# frankfurt_eth_pic.net
KiCad netlist of a schematic drawn in EAGLE
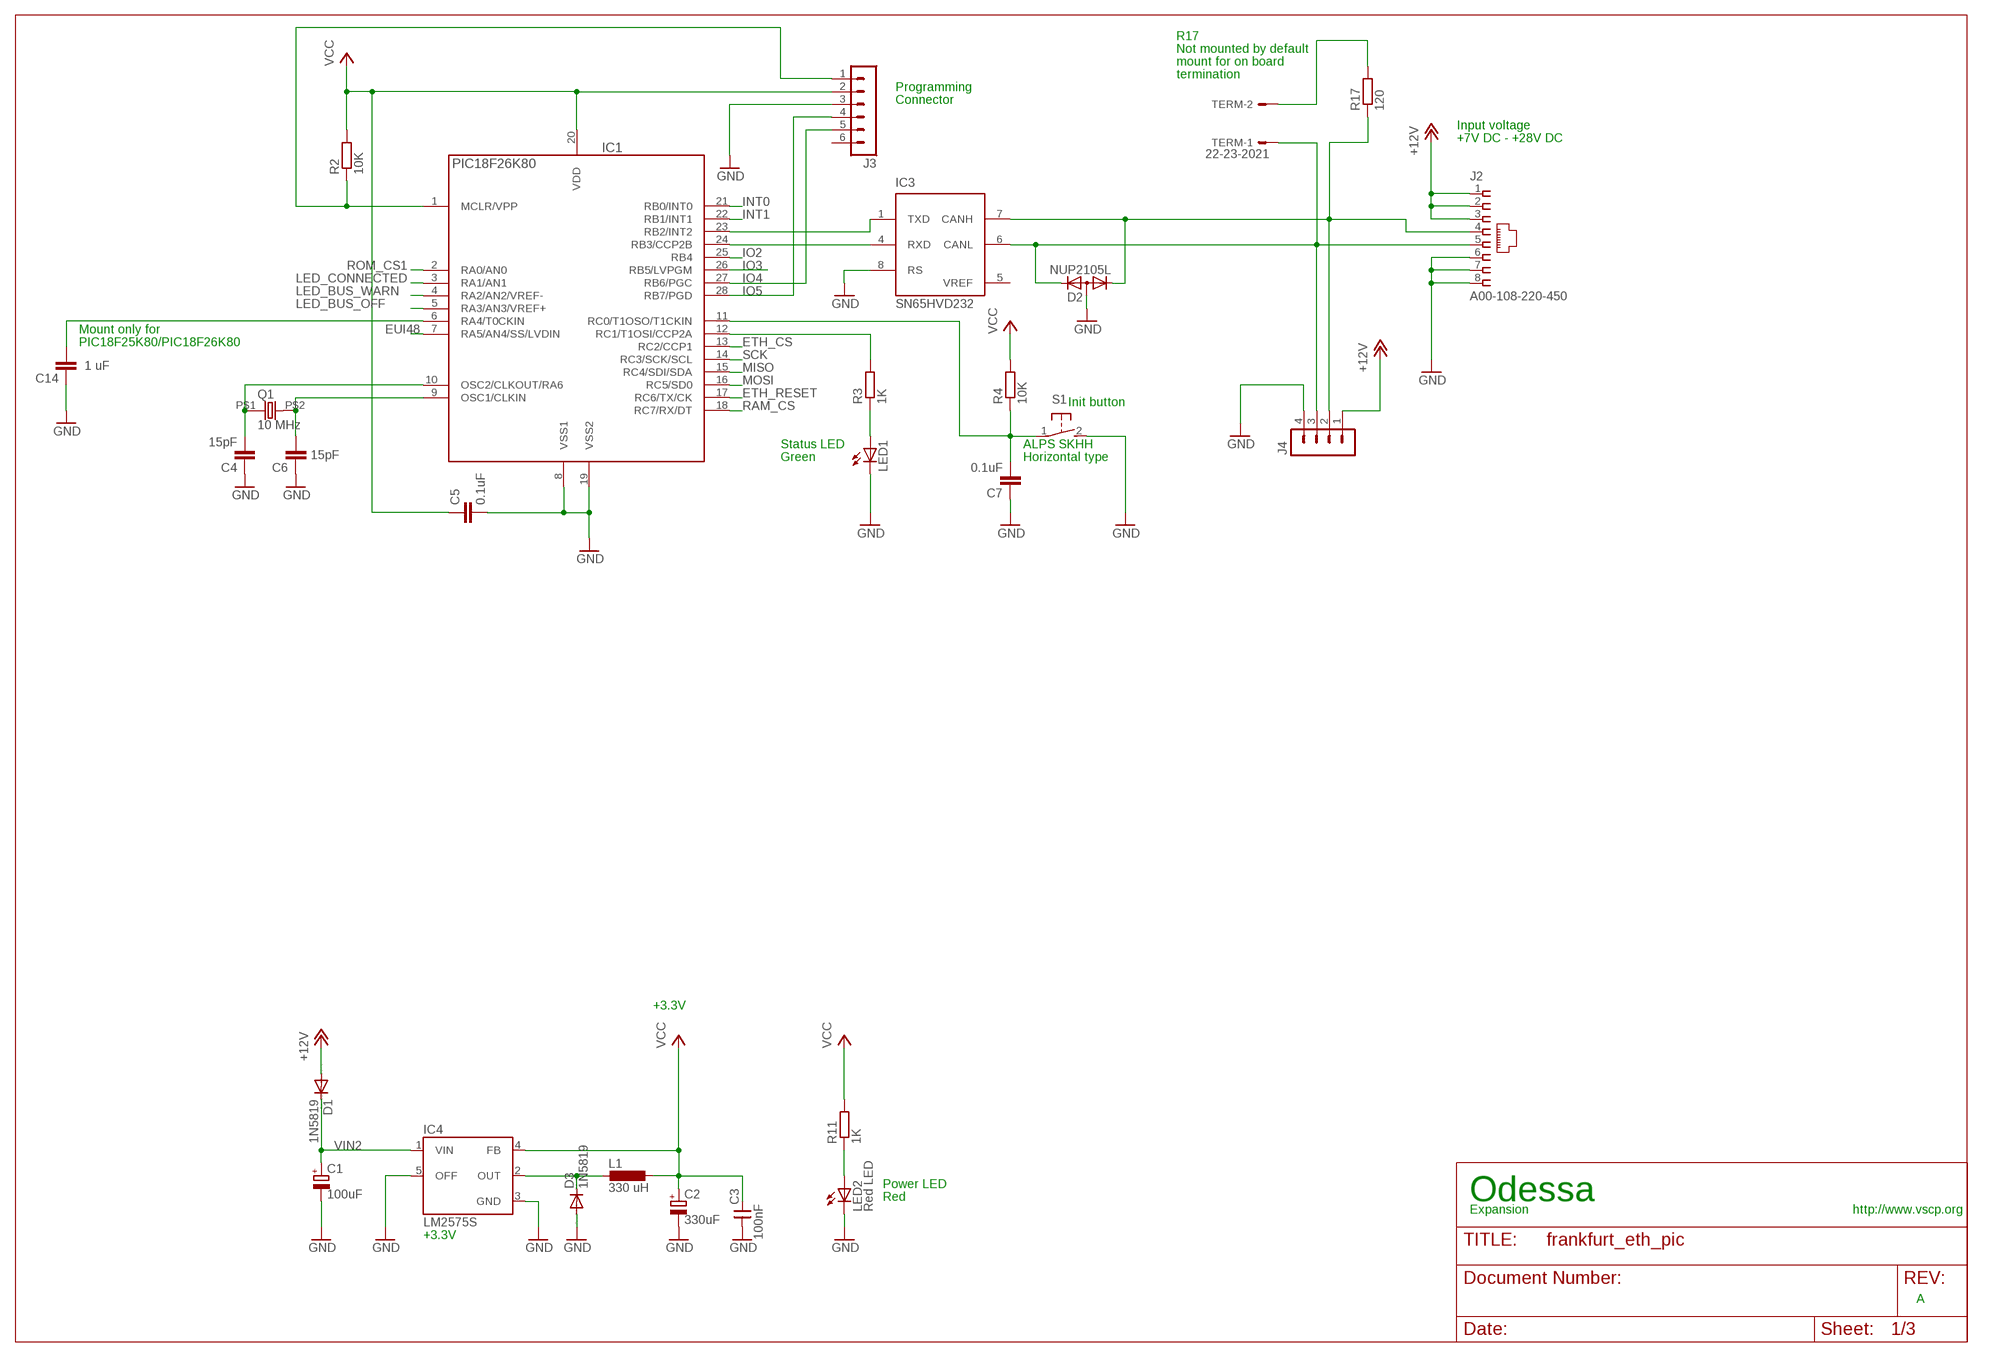
[diagram p0: schematic, sheet 1]
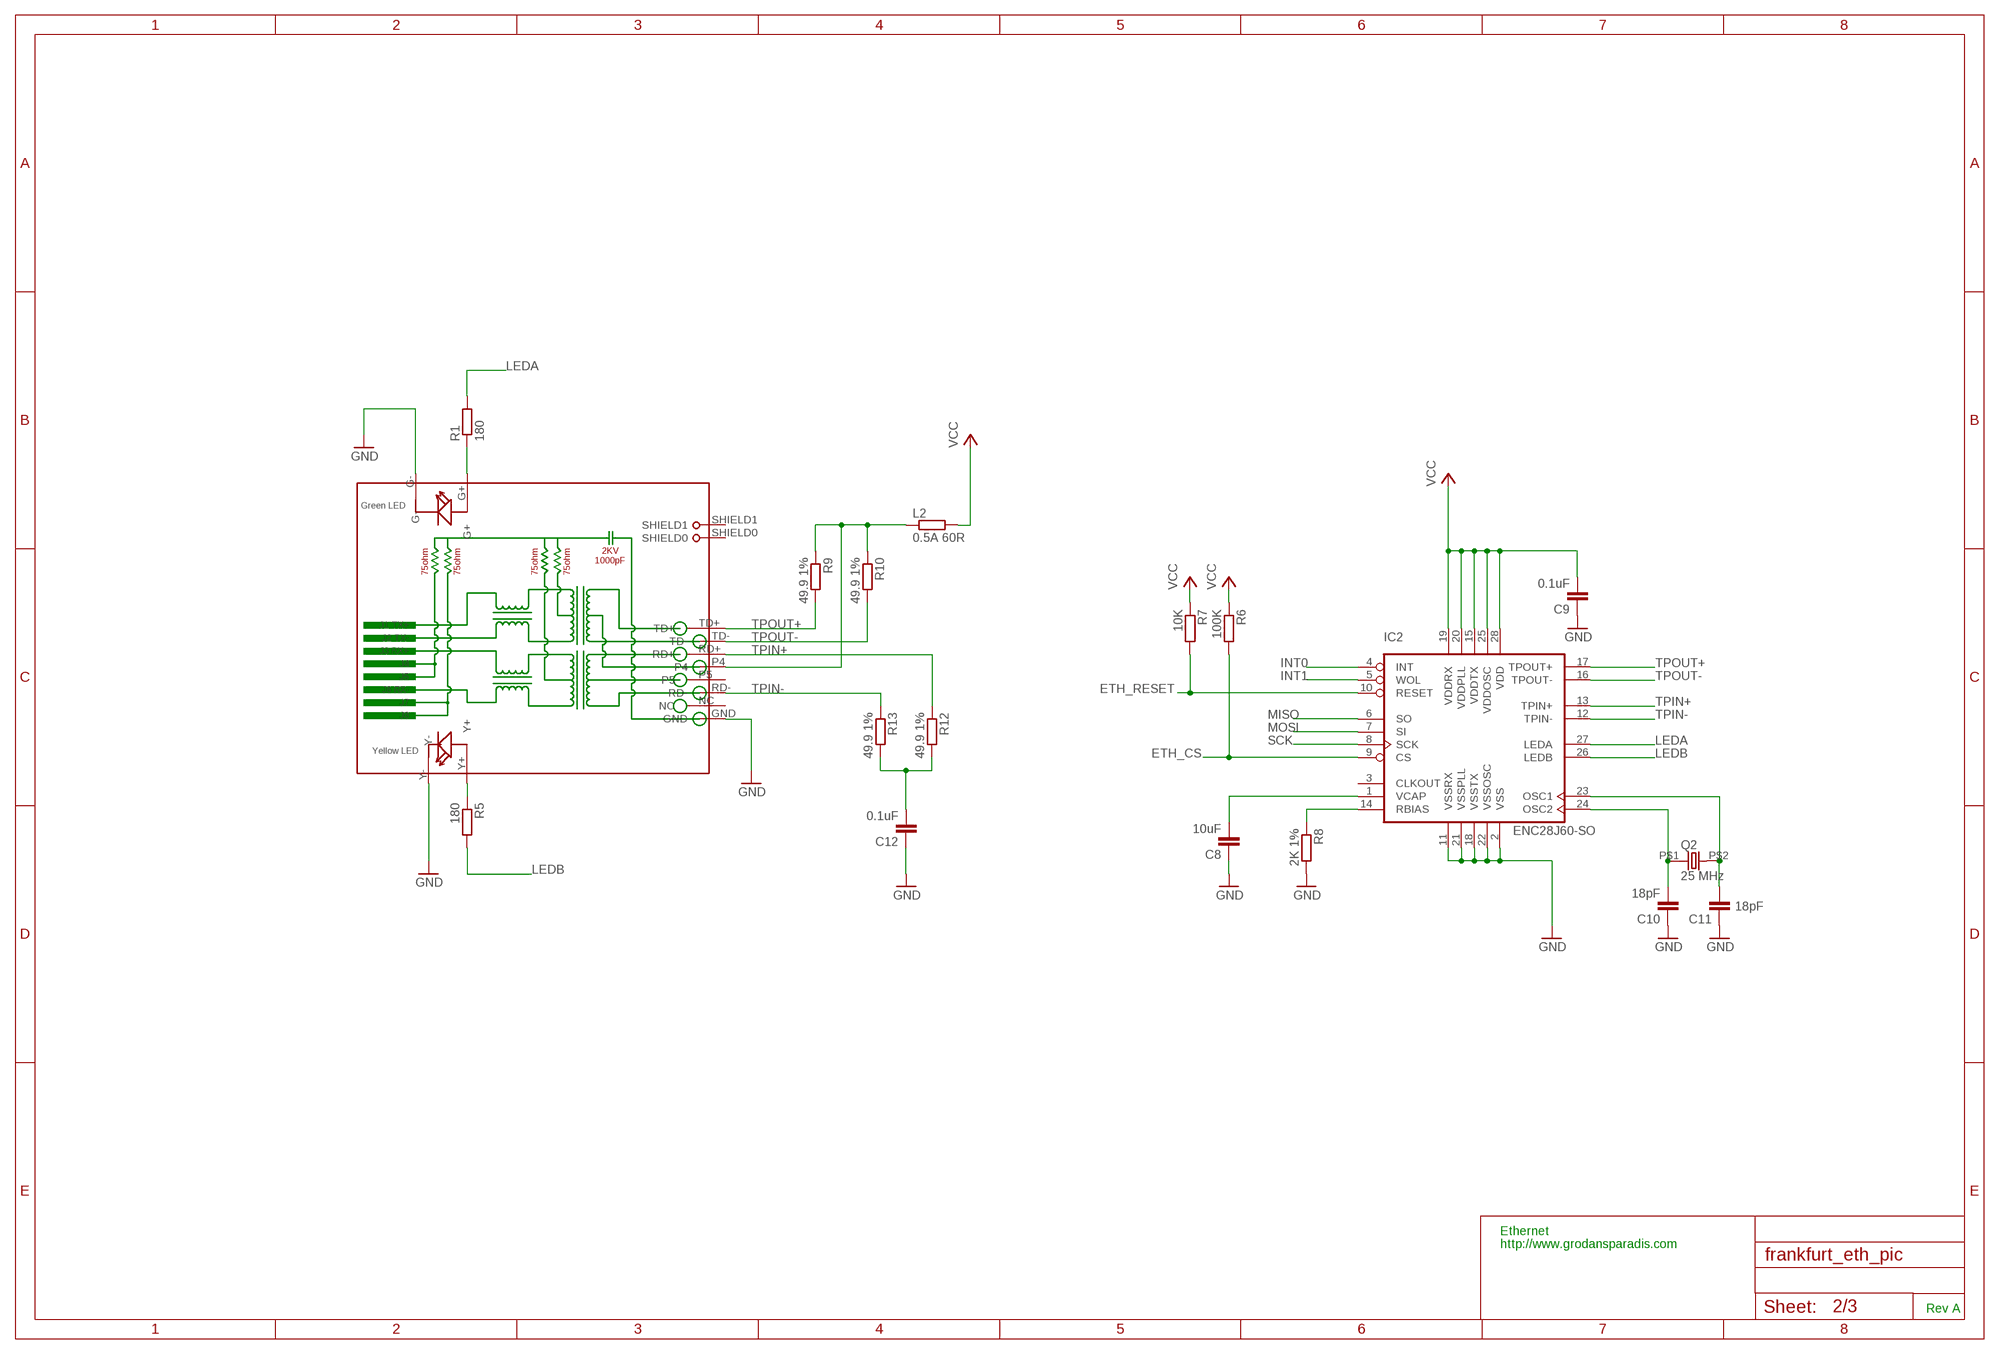
[diagram p1: schematic, sheet 2]
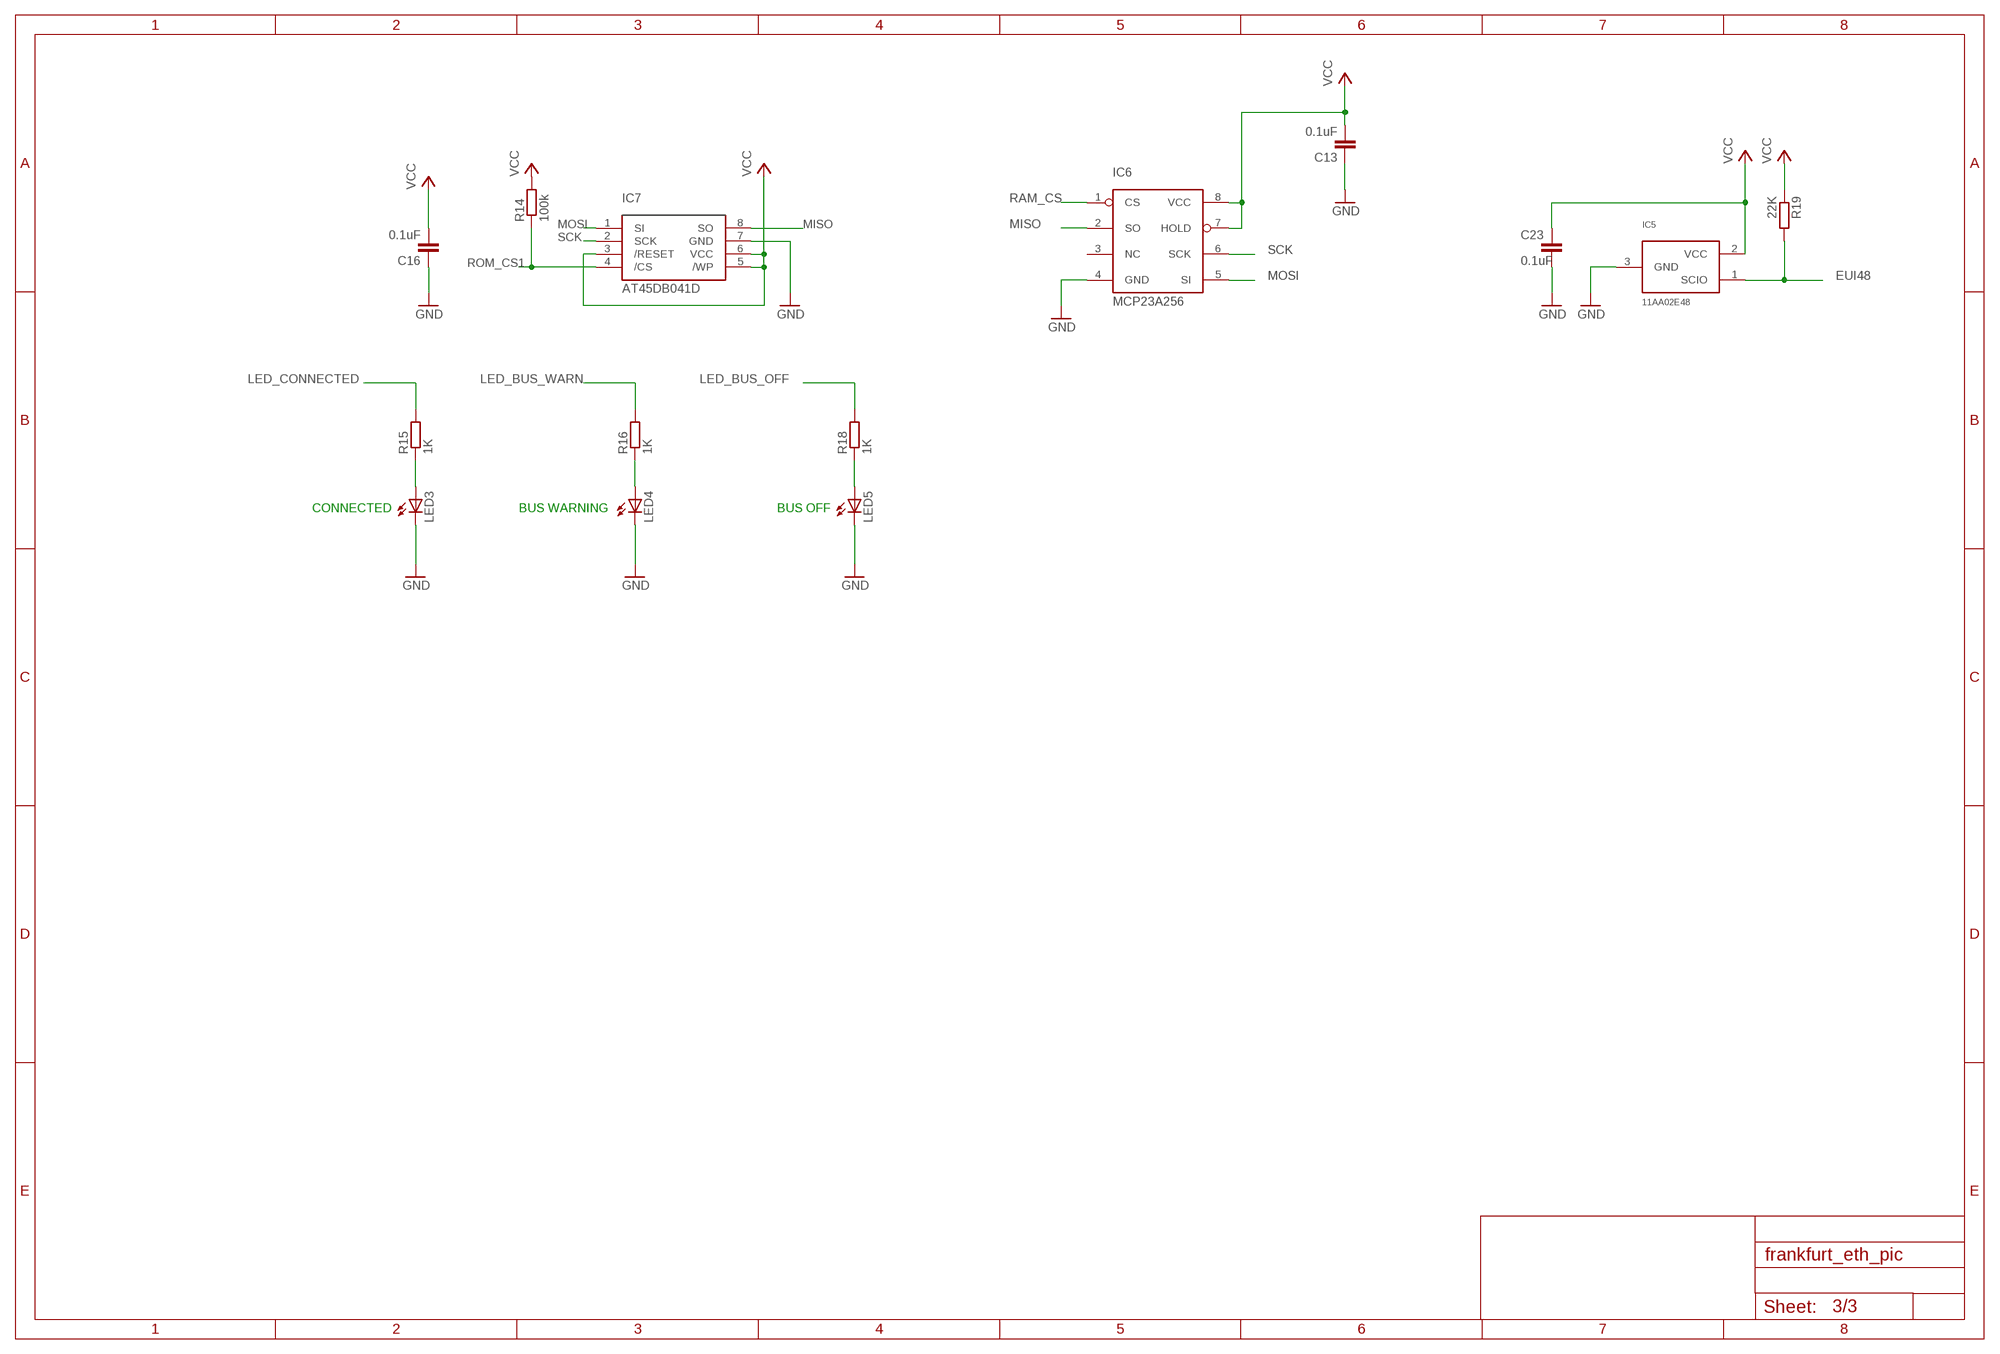
[diagram p2: schematic, sheet 3]

(export (version "E")
  (design (tool "Eeschema 10.0.6"))
  (components
    (comp (ref "C8")
      (value "10uF")
      (footprint "eagle-import:C0805")
      (libsource (lib "eagle-import") (part "C-EUC0805"))
    )
    (comp (ref "C9")
      (value "0.1uF")
      (footprint "eagle-import:C0805")
      (libsource (lib "eagle-import") (part "C-EUC0805"))
    )
    (comp (ref "C10")
      (value "18pF")
      (footprint "eagle-import:C0805")
      (libsource (lib "eagle-import") (part "C-EUC0805"))
    )
    (comp (ref "C11")
      (value "18pF")
      (footprint "eagle-import:C0805")
      (libsource (lib "eagle-import") (part "C-EUC0805"))
    )
    (comp (ref "C12")
      (value "0.1uF")
      (footprint "eagle-import:C0805")
      (libsource (lib "eagle-import") (part "C-EUC0805"))
    )
    (comp (ref "IC2")
      (value "ENC28J60-SO")
      (footprint "eagle-import:SO28W")
      (libsource (lib "eagle-import") (part "ENC28J60-SO"))
    )
    (comp (ref "L2")
      (value "0.5A 60R")
      (footprint "eagle-import:R0805")
      (libsource (lib "eagle-import") (part "R-EU_R0805"))
    )
    (comp (ref "Q2")
      (value "25 MHz")
      (footprint "eagle-import:9C")
      (libsource (lib "eagle-import") (part "HC-49S"))
    )
    (comp (ref "R1")
      (value "180")
      (footprint "eagle-import:R0805")
      (libsource (lib "eagle-import") (part "R-EU_R0805"))
    )
    (comp (ref "R5")
      (value "180")
      (footprint "eagle-import:R0805")
      (libsource (lib "eagle-import") (part "R-EU_R0805"))
    )
    (comp (ref "R6")
      (value "100K")
      (footprint "eagle-import:R0805")
      (libsource (lib "eagle-import") (part "R-EU_R0805"))
    )
    (comp (ref "R7")
      (value "10K")
      (footprint "eagle-import:R0805")
      (libsource (lib "eagle-import") (part "R-EU_R0805"))
    )
    (comp (ref "R8")
      (value "2K 1%")
      (footprint "eagle-import:R0805")
      (libsource (lib "eagle-import") (part "R-EU_R0805"))
    )
    (comp (ref "R9")
      (value "49.9 1%")
      (footprint "eagle-import:R0805")
      (libsource (lib "eagle-import") (part "R-EU_R0805"))
    )
    (comp (ref "R10")
      (value "49.9 1%")
      (footprint "eagle-import:R0805")
      (libsource (lib "eagle-import") (part "R-EU_R0805"))
    )
    (comp (ref "R12")
      (value "49.9 1%")
      (footprint "eagle-import:R0805")
      (libsource (lib "eagle-import") (part "R-EU_R0805"))
    )
    (comp (ref "R13")
      (value "49.9 1%")
      (footprint "eagle-import:R0805")
      (libsource (lib "eagle-import") (part "R-EU_R0805"))
    )
    (comp (ref "RJ1")
      (value "HR911105A")
      (footprint "eagle-import:HR911105A")
      (libsource (lib "eagle-import") (part "HR911105A"))
    )
    (comp (ref "C13")
      (value "0.1uF")
      (footprint "eagle-import:C0805")
      (libsource (lib "eagle-import") (part "C-EUC0805"))
    )
    (comp (ref "C16")
      (value "0.1uF")
      (footprint "eagle-import:C0805")
      (libsource (lib "eagle-import") (part "C-EUC0805"))
    )
    (comp (ref "C23")
      (value "0.1uF")
      (footprint "eagle-import:C0805")
      (libsource (lib "eagle-import") (part "C-EUC0805"))
    )
    (comp (ref "IC5")
      (value "11AA02E48")
      (footprint "eagle-import:SOT23")
      (libsource (lib "eagle-import") (part "11AA02E48"))
    )
    (comp (ref "IC6")
      (value "MCP23A256")
      (footprint "eagle-import:SO-8")
      (libsource (lib "eagle-import") (part "MCP23A256"))
    )
    (comp (ref "IC7")
      (value "AT45DB041D")
      (footprint "eagle-import:SOP8W")
      (libsource (lib "eagle-import") (part "AT45DB011DSOP8W"))
    )
    (comp (ref "LED3")
      (value "LEDCHIP-LED0805")
      (footprint "eagle-import:CHIP-LED0805")
      (libsource (lib "eagle-import") (part "LEDCHIP-LED0805"))
    )
    (comp (ref "LED4")
      (value "LEDCHIP-LED0805")
      (footprint "eagle-import:CHIP-LED0805")
      (libsource (lib "eagle-import") (part "LEDCHIP-LED0805"))
    )
    (comp (ref "LED5")
      (value "LEDCHIP-LED0805")
      (footprint "eagle-import:CHIP-LED0805")
      (libsource (lib "eagle-import") (part "LEDCHIP-LED0805"))
    )
    (comp (ref "R14")
      (value "100k")
      (footprint "eagle-import:M0805")
      (libsource (lib "eagle-import") (part "R-EU_M0805"))
    )
    (comp (ref "R15")
      (value "1K")
      (footprint "eagle-import:R0805")
      (libsource (lib "eagle-import") (part "R-EU_R0805"))
    )
    (comp (ref "R16")
      (value "1K")
      (footprint "eagle-import:R0805")
      (libsource (lib "eagle-import") (part "R-EU_R0805"))
    )
    (comp (ref "R18")
      (value "1K")
      (footprint "eagle-import:R0805")
      (libsource (lib "eagle-import") (part "R-EU_R0805"))
    )
    (comp (ref "R19")
      (value "22K")
      (footprint "eagle-import:M0805")
      (libsource (lib "eagle-import") (part "R-EU_M0805"))
    )
    (comp (ref "C1")
      (value "100uF")
      (footprint "eagle-import:PANASONIC_D")
      (libsource (lib "eagle-import") (part "CPOL-EUD"))
    )
    (comp (ref "C2")
      (value "330uF")
      (footprint "eagle-import:PANASONIC_D")
      (libsource (lib "eagle-import") (part "CPOL-EUD"))
    )
    (comp (ref "C3")
      (value "100nF")
      (footprint "eagle-import:0805")
      (libsource (lib "eagle-import") (part "CNP-0805"))
    )
    (comp (ref "C4")
      (value "15pF")
      (footprint "eagle-import:C0805")
      (libsource (lib "eagle-import") (part "C-EUC0805"))
    )
    (comp (ref "C5")
      (value "0.1uF")
      (footprint "eagle-import:C0805")
      (libsource (lib "eagle-import") (part "C-EUC0805"))
    )
    (comp (ref "C6")
      (value "15pF")
      (footprint "eagle-import:C0805")
      (libsource (lib "eagle-import") (part "C-EUC0805"))
    )
    (comp (ref "C7")
      (value "0.1uF")
      (footprint "eagle-import:C0805")
      (libsource (lib "eagle-import") (part "C-EUC0805"))
    )
    (comp (ref "C14")
      (value "1 uF")
      (footprint "eagle-import:C0805")
      (libsource (lib "eagle-import") (part "C-EUC0805"))
    )
    (comp (ref "D1")
      (value "1N5819")
      (footprint "eagle-import:SOD123")
      (libsource (lib "eagle-import") (part "DIODE-SOD123"))
    )
    (comp (ref "D2")
      (value "NUP2105L")
      (footprint "eagle-import:SOT23")
      (libsource (lib "eagle-import") (part "DIODE-2CA|ACSOT23"))
    )
    (comp (ref "D3")
      (value "1N5819")
      (footprint "eagle-import:SOD123")
      (libsource (lib "eagle-import") (part "DIODE-SOD123"))
    )
    (comp (ref "IC1")
      (value "PIC18F26K80")
      (footprint "eagle-import:SO28")
      (libsource (lib "eagle-import") (part "PIC18F252-?I/SOL"))
    )
    (comp (ref "IC3")
      (value "SN65HVD232")
      (footprint "eagle-import:SO-08")
      (libsource (lib "eagle-import") (part "MCP2551SN"))
    )
    (comp (ref "IC4")
      (value "LM2575S")
      (footprint "eagle-import:TO263-5")
      (libsource (lib "eagle-import") (part "LM2575S"))
    )
    (comp (ref "J2")
      (value "A00-108-220-450")
      (footprint "eagle-import:RJ-45")
      (libsource (lib "eagle-import") (part "A00-108-220-450"))
    )
    (comp (ref "J3")
      (value "MA06-1")
      (footprint "eagle-import:MA06-1")
      (libsource (lib "eagle-import") (part "MA06-1"))
    )
    (comp (ref "J4")
      (value "MA04-1")
      (footprint "eagle-import:MA04-1")
      (libsource (lib "eagle-import") (part "MA04-1"))
    )
    (comp (ref "L1")
      (value "330 uH")
      (footprint "eagle-import:DO3316P")
      (libsource (lib "eagle-import") (part "DO3316P"))
    )
    (comp (ref "LED1")
      (value "LEDCHIP-LED0805")
      (footprint "eagle-import:CHIP-LED0805")
      (libsource (lib "eagle-import") (part "LEDCHIP-LED0805"))
    )
    (comp (ref "LED2")
      (value "Red LED")
      (footprint "eagle-import:CHIP-LED0805")
      (libsource (lib "eagle-import") (part "LEDCHIP-LED0805"))
    )
    (comp (ref "Q1")
      (value "10 MHz")
      (footprint "eagle-import:9C")
      (libsource (lib "eagle-import") (part "HC-49S"))
    )
    (comp (ref "R2")
      (value "10K")
      (footprint "eagle-import:R0805")
      (libsource (lib "eagle-import") (part "R-EU_R0805"))
    )
    (comp (ref "R3")
      (value "1K")
      (footprint "eagle-import:R0805")
      (libsource (lib "eagle-import") (part "R-EU_R0805"))
    )
    (comp (ref "R4")
      (value "10K")
      (footprint "eagle-import:R0805")
      (libsource (lib "eagle-import") (part "R-EU_R0805"))
    )
    (comp (ref "R11")
      (value "1K")
      (footprint "eagle-import:R0805")
      (libsource (lib "eagle-import") (part "R-EU_R0805"))
    )
    (comp (ref "R17")
      (value "120")
      (footprint "eagle-import:R0805")
      (libsource (lib "eagle-import") (part "R-EU_R0805"))
    )
    (comp (ref "S1")
      (value "31-XX")
      (footprint "eagle-import:B3F-31XX")
      (fields (field (name "MPN") "B3F-3100"))
      (libsource (lib "eagle-import") (part "31-XX"))
    )
    (comp (ref "TERM")
      (value "22-23-2021")
      (footprint "eagle-import:22-23-2021")
      (fields (field (name "MF") "MOLEX"))
      (libsource (lib "eagle-import") (part "22-23-2021"))
    )
  )
  (nets
    (net (code "1") (name "+12V") (class "Default")
      (node (ref "D1") (pin "A") (pinfunction "A_A") (pintype "passive"))
      (node (ref "J2") (pin "1") (pinfunction "1_1") (pintype "passive"))
      (node (ref "J2") (pin "2") (pinfunction "2_2") (pintype "passive"))
      (node (ref "J2") (pin "3") (pinfunction "3_3") (pintype "passive"))
      (node (ref "J4") (pin "1") (pinfunction "1_1") (pintype "passive"))
    )
    (net (code "2") (name "ETH_CS") (class "Default")
      (node (ref "IC1") (pin "13") (pinfunction "RC2/CCP1_13") (pintype "bidirectional"))
      (node (ref "IC2") (pin "9") (pinfunction "CS_9") (pintype "input"))
      (node (ref "R6") (pin "2") (pinfunction "2_2") (pintype "passive"))
    )
    (net (code "3") (name "ETH_RESET") (class "Default")
      (node (ref "IC1") (pin "17") (pinfunction "RC6/TX/CK_17") (pintype "bidirectional"))
      (node (ref "IC2") (pin "10") (pinfunction "RESET_10") (pintype "input"))
      (node (ref "R7") (pin "2") (pinfunction "2_2") (pintype "passive"))
    )
    (net (code "4") (name "EUI48") (class "Default")
      (node (ref "IC1") (pin "7") (pinfunction "RA5/AN4/SS/LVDIN_7") (pintype "bidirectional"))
      (node (ref "IC5") (pin "1") (pinfunction "SCIO_1") (pintype "bidirectional"))
      (node (ref "R19") (pin "2") (pinfunction "2_2") (pintype "passive"))
    )
    (net (code "5") (name "GND") (class "Default")
      (node (ref "C1") (pin "-") (pinfunction "-_-") (pintype "passive"))
      (node (ref "C10") (pin "1") (pinfunction "1_1") (pintype "passive"))
      (node (ref "C11") (pin "1") (pinfunction "1_1") (pintype "passive"))
      (node (ref "C12") (pin "1") (pinfunction "1_1") (pintype "passive"))
      (node (ref "C13") (pin "1") (pinfunction "1_1") (pintype "passive"))
      (node (ref "C14") (pin "1") (pinfunction "1_1") (pintype "passive"))
      (node (ref "C16") (pin "1") (pinfunction "1_1") (pintype "passive"))
      (node (ref "C2") (pin "-") (pinfunction "-_-") (pintype "passive"))
      (node (ref "C23") (pin "2") (pinfunction "2_2") (pintype "passive"))
      (node (ref "C3") (pin "1") (pinfunction "1_1") (pintype "passive"))
      (node (ref "C4") (pin "1") (pinfunction "1_1") (pintype "passive"))
      (node (ref "C5") (pin "2") (pinfunction "2_2") (pintype "passive"))
      (node (ref "C6") (pin "1") (pinfunction "1_1") (pintype "passive"))
      (node (ref "C7") (pin "1") (pinfunction "1_1") (pintype "passive"))
      (node (ref "C8") (pin "1") (pinfunction "1_1") (pintype "passive"))
      (node (ref "C9") (pin "1") (pinfunction "1_1") (pintype "passive"))
      (node (ref "D2") (pin "3") (pinfunction "A_3") (pintype "passive"))
      (node (ref "D3") (pin "A") (pinfunction "A_A") (pintype "passive"))
      (node (ref "IC1") (pin "19") (pinfunction "VSS2_19") (pintype "power_in"))
      (node (ref "IC1") (pin "8") (pinfunction "VSS1_8") (pintype "power_in"))
      (node (ref "IC2") (pin "11") (pinfunction "VSSRX_11") (pintype "power_in"))
      (node (ref "IC2") (pin "18") (pinfunction "VSSTX_18") (pintype "power_in"))
      (node (ref "IC2") (pin "2") (pinfunction "VSS_2") (pintype "power_in"))
      (node (ref "IC2") (pin "21") (pinfunction "VSSPLL_21") (pintype "power_in"))
      (node (ref "IC2") (pin "22") (pinfunction "VSSOSC_22") (pintype "power_in"))
      (node (ref "IC3") (pin "8") (pinfunction "RS_8") (pintype "input"))
      (node (ref "IC4") (pin "3") (pinfunction "GND_3") (pintype "power_in"))
      (node (ref "IC4") (pin "5") (pinfunction "OFF_5") (pintype "input"))
      (node (ref "IC5") (pin "3") (pinfunction "GND_3") (pintype "power_in"))
      (node (ref "IC6") (pin "4") (pinfunction "GND_4") (pintype "power_in"))
      (node (ref "IC7") (pin "7") (pinfunction "GND_7") (pintype "power_in"))
      (node (ref "J2") (pin "6") (pinfunction "6_6") (pintype "passive"))
      (node (ref "J2") (pin "7") (pinfunction "7_7") (pintype "passive"))
      (node (ref "J2") (pin "8") (pinfunction "8_8") (pintype "passive"))
      (node (ref "J3") (pin "3") (pinfunction "3_3") (pintype "passive"))
      (node (ref "J4") (pin "4") (pinfunction "4_4") (pintype "passive"))
      (node (ref "LED1") (pin "C") (pinfunction "C_C") (pintype "passive"))
      (node (ref "LED2") (pin "C") (pinfunction "C_C") (pintype "passive"))
      (node (ref "LED3") (pin "C") (pinfunction "C_C") (pintype "passive"))
      (node (ref "LED4") (pin "C") (pinfunction "C_C") (pintype "passive"))
      (node (ref "LED5") (pin "C") (pinfunction "C_C") (pintype "passive"))
      (node (ref "R8") (pin "2") (pinfunction "2_2") (pintype "passive"))
      (node (ref "RJ1") (pin "G-") (pinfunction "G-_G-") (pintype "bidirectional"))
      (node (ref "RJ1") (pin "GND") (pinfunction "GND_GND") (pintype "bidirectional"))
      (node (ref "RJ1") (pin "Y-") (pinfunction "Y-_Y-") (pintype "bidirectional"))
      (node (ref "S1") (pin "2") (pinfunction "S_2") (pintype "passive"))
    )
    (net (code "6") (name "INT0") (class "Default")
      (node (ref "IC1") (pin "21") (pinfunction "RB0/INT0_21") (pintype "bidirectional"))
      (node (ref "IC2") (pin "4") (pinfunction "INT_4") (pintype "output"))
    )
    (net (code "7") (name "INT1") (class "Default")
      (node (ref "IC1") (pin "22") (pinfunction "RB1/INT1_22") (pintype "bidirectional"))
      (node (ref "IC2") (pin "5") (pinfunction "WOL_5") (pintype "output"))
    )
    (net (code "8") (name "IO2") (class "Default")
      (node (ref "IC1") (pin "25") (pinfunction "RB4_25") (pintype "bidirectional"))
    )
    (net (code "9") (name "IO3") (class "Default")
      (node (ref "IC1") (pin "26") (pinfunction "RB5/LVPGM_26") (pintype "bidirectional"))
    )
    (net (code "10") (name "IO4") (class "Default")
      (node (ref "IC1") (pin "27") (pinfunction "RB6/PGC_27") (pintype "bidirectional"))
      (node (ref "J3") (pin "5") (pinfunction "5_5") (pintype "passive"))
    )
    (net (code "11") (name "IO5") (class "Default")
      (node (ref "IC1") (pin "28") (pinfunction "RB7/PGD_28") (pintype "bidirectional"))
      (node (ref "J3") (pin "4") (pinfunction "4_4") (pintype "passive"))
    )
    (net (code "12") (name "LEDA") (class "Default")
      (node (ref "IC2") (pin "27") (pinfunction "LEDA_27") (pintype "output"))
      (node (ref "R1") (pin "2") (pinfunction "2_2") (pintype "passive"))
    )
    (net (code "13") (name "LEDB") (class "Default")
      (node (ref "IC2") (pin "26") (pinfunction "LEDB_26") (pintype "output"))
      (node (ref "R5") (pin "2") (pinfunction "2_2") (pintype "passive"))
    )
    (net (code "14") (name "LED_BUS_OFF") (class "Default")
      (node (ref "IC1") (pin "5") (pinfunction "RA3/AN3/VREF+_5") (pintype "bidirectional"))
      (node (ref "R18") (pin "2") (pinfunction "2_2") (pintype "passive"))
    )
    (net (code "15") (name "LED_BUS_WARN") (class "Default")
      (node (ref "IC1") (pin "4") (pinfunction "RA2/AN2/VREF-_4") (pintype "bidirectional"))
      (node (ref "R16") (pin "2") (pinfunction "2_2") (pintype "passive"))
    )
    (net (code "16") (name "LED_CONNECTED") (class "Default")
      (node (ref "IC1") (pin "3") (pinfunction "RA1/AN1_3") (pintype "bidirectional"))
      (node (ref "R15") (pin "2") (pinfunction "2_2") (pintype "passive"))
    )
    (net (code "17") (name "MISO") (class "Default")
      (node (ref "IC1") (pin "15") (pinfunction "RC4/SDI/SDA_15") (pintype "bidirectional"))
      (node (ref "IC2") (pin "6") (pinfunction "SO_6") (pintype "output"))
      (node (ref "IC6") (pin "2") (pinfunction "SO_2") (pintype "output"))
      (node (ref "IC7") (pin "8") (pinfunction "SO_8") (pintype "output"))
    )
    (net (code "18") (name "MOSI") (class "Default")
      (node (ref "IC1") (pin "16") (pinfunction "RC5/SD0_16") (pintype "bidirectional"))
      (node (ref "IC2") (pin "7") (pinfunction "SI_7") (pintype "input"))
      (node (ref "IC6") (pin "5") (pinfunction "SI_5") (pintype "input"))
      (node (ref "IC7") (pin "1") (pinfunction "SI_1") (pintype "input"))
    )
    (net (code "19") (name "Net-(C12-Pad2)") (class "Default")
      (node (ref "C12") (pin "2") (pinfunction "2_2") (pintype "passive"))
      (node (ref "R12") (pin "2") (pinfunction "2_2") (pintype "passive"))
      (node (ref "R13") (pin "2") (pinfunction "2_2") (pintype "passive"))
    )
    (net (code "20") (name "Net-(D2-K1)") (class "Default")
      (node (ref "D2") (pin "1") (pinfunction "K1_1") (pintype "passive"))
      (node (ref "IC3") (pin "7") (pinfunction "CANH_7") (pintype "bidirectional"))
      (node (ref "J2") (pin "4") (pinfunction "4_4") (pintype "passive"))
      (node (ref "J4") (pin "2") (pinfunction "2_2") (pintype "passive"))
      (node (ref "R17") (pin "1") (pinfunction "1_1") (pintype "passive"))
    )
    (net (code "21") (name "Net-(D2-K2)") (class "Default")
      (node (ref "D2") (pin "2") (pinfunction "K2_2") (pintype "passive"))
      (node (ref "IC3") (pin "6") (pinfunction "CANL_6") (pintype "bidirectional"))
      (node (ref "J2") (pin "5") (pinfunction "5_5") (pintype "passive"))
      (node (ref "J4") (pin "3") (pinfunction "3_3") (pintype "passive"))
      (node (ref "TERM") (pin "1") (pinfunction "S_1") (pintype "passive"))
    )
    (net (code "22") (name "Net-(IC1-MCLR{slash}VPP)") (class "Default")
      (node (ref "IC1") (pin "1") (pinfunction "MCLR/VPP_1") (pintype "input"))
      (node (ref "J3") (pin "1") (pinfunction "1_1") (pintype "passive"))
      (node (ref "R2") (pin "1") (pinfunction "1_1") (pintype "passive"))
    )
    (net (code "23") (name "Net-(IC1-OSC1{slash}CLKIN)") (class "Default")
      (node (ref "C6") (pin "2") (pinfunction "2_2") (pintype "passive"))
      (node (ref "IC1") (pin "9") (pinfunction "OSC1/CLKIN_9") (pintype "input"))
      (node (ref "Q1") (pin "P$2") (pinfunction "2_P$2") (pintype "passive"))
    )
    (net (code "24") (name "Net-(IC1-OSC2{slash}CLKOUT{slash}RA6)") (class "Default")
      (node (ref "C4") (pin "2") (pinfunction "2_2") (pintype "passive"))
      (node (ref "IC1") (pin "10") (pinfunction "OSC2/CLKOUT/RA6_10") (pintype "output"))
      (node (ref "Q1") (pin "P$1") (pinfunction "1_P$1") (pintype "passive"))
    )
    (net (code "25") (name "Net-(IC1-RA4{slash}T0CKIN)") (class "Default")
      (node (ref "C14") (pin "2") (pinfunction "2_2") (pintype "passive"))
      (node (ref "IC1") (pin "6") (pinfunction "RA4/T0CKIN_6") (pintype "open_collector"))
    )
    (net (code "26") (name "Net-(IC1-RB2{slash}INT2)") (class "Default")
      (node (ref "IC1") (pin "23") (pinfunction "RB2/INT2_23") (pintype "bidirectional"))
      (node (ref "IC3") (pin "1") (pinfunction "TXD_1") (pintype "input"))
    )
    (net (code "27") (name "Net-(IC1-RB3{slash}CCP2B)") (class "Default")
      (node (ref "IC1") (pin "24") (pinfunction "RB3/CCP2B_24") (pintype "bidirectional"))
      (node (ref "IC3") (pin "4") (pinfunction "RXD_4") (pintype "output"))
    )
    (net (code "28") (name "Net-(IC1-RC0{slash}T1OSO{slash}T1CKIN)") (class "Default")
      (node (ref "C7") (pin "2") (pinfunction "2_2") (pintype "passive"))
      (node (ref "IC1") (pin "11") (pinfunction "RC0/T1OSO/T1CKIN_11") (pintype "bidirectional"))
      (node (ref "R4") (pin "1") (pinfunction "1_1") (pintype "passive"))
      (node (ref "S1") (pin "1") (pinfunction "P_1") (pintype "passive"))
    )
    (net (code "29") (name "Net-(IC1-RC1{slash}T1OSI{slash}CCP2A)") (class "Default")
      (node (ref "IC1") (pin "12") (pinfunction "RC1/T1OSI/CCP2A_12") (pintype "bidirectional"))
      (node (ref "R3") (pin "2") (pinfunction "2_2") (pintype "passive"))
    )
    (net (code "30") (name "Net-(IC2-OSC1)") (class "Default")
      (node (ref "C11") (pin "2") (pinfunction "2_2") (pintype "passive"))
      (node (ref "IC2") (pin "23") (pinfunction "OSC1_23") (pintype "input"))
      (node (ref "Q2") (pin "P$2") (pinfunction "2_P$2") (pintype "passive"))
    )
    (net (code "31") (name "Net-(IC2-OSC2)") (class "Default")
      (node (ref "C10") (pin "2") (pinfunction "2_2") (pintype "passive"))
      (node (ref "IC2") (pin "24") (pinfunction "OSC2_24") (pintype "output"))
      (node (ref "Q2") (pin "P$1") (pinfunction "1_P$1") (pintype "passive"))
    )
    (net (code "32") (name "Net-(IC2-RBIAS)") (class "Default")
      (node (ref "IC2") (pin "14") (pinfunction "RBIAS_14") (pintype "passive"))
      (node (ref "R8") (pin "1") (pinfunction "1_1") (pintype "passive"))
    )
    (net (code "33") (name "Net-(IC2-VCAP)") (class "Default")
      (node (ref "C8") (pin "2") (pinfunction "2_2") (pintype "passive"))
      (node (ref "IC2") (pin "1") (pinfunction "VCAP_1") (pintype "power_in"))
    )
    (net (code "34") (name "Net-(IC4-OUT)") (class "Default")
      (node (ref "D3") (pin "C") (pinfunction "C_C") (pintype "passive"))
      (node (ref "IC4") (pin "2") (pinfunction "OUT_2") (pintype "output"))
      (node (ref "L1") (pin "1") (pinfunction "1_1") (pintype "passive"))
    )
    (net (code "35") (name "Net-(L2-Pad1)") (class "Default")
      (node (ref "L2") (pin "1") (pinfunction "1_1") (pintype "passive"))
      (node (ref "R10") (pin "1") (pinfunction "1_1") (pintype "passive"))
      (node (ref "R9") (pin "1") (pinfunction "1_1") (pintype "passive"))
      (node (ref "RJ1") (pin "P4") (pinfunction "P4_P4") (pintype "bidirectional"))
    )
    (net (code "36") (name "Net-(LED1-PadA)") (class "Default")
      (node (ref "LED1") (pin "A") (pinfunction "A_A") (pintype "passive"))
      (node (ref "R3") (pin "1") (pinfunction "1_1") (pintype "passive"))
    )
    (net (code "37") (name "Net-(LED2-PadA)") (class "Default")
      (node (ref "LED2") (pin "A") (pinfunction "A_A") (pintype "passive"))
      (node (ref "R11") (pin "1") (pinfunction "1_1") (pintype "passive"))
    )
    (net (code "38") (name "Net-(LED3-PadA)") (class "Default")
      (node (ref "LED3") (pin "A") (pinfunction "A_A") (pintype "passive"))
      (node (ref "R15") (pin "1") (pinfunction "1_1") (pintype "passive"))
    )
    (net (code "39") (name "Net-(LED4-PadA)") (class "Default")
      (node (ref "LED4") (pin "A") (pinfunction "A_A") (pintype "passive"))
      (node (ref "R16") (pin "1") (pinfunction "1_1") (pintype "passive"))
    )
    (net (code "40") (name "Net-(LED5-PadA)") (class "Default")
      (node (ref "LED5") (pin "A") (pinfunction "A_A") (pintype "passive"))
      (node (ref "R18") (pin "1") (pinfunction "1_1") (pintype "passive"))
    )
    (net (code "41") (name "Net-(R1-Pad1)") (class "Default")
      (node (ref "R1") (pin "1") (pinfunction "1_1") (pintype "passive"))
      (node (ref "RJ1") (pin "G+") (pinfunction "G+_G+") (pintype "bidirectional"))
    )
    (net (code "42") (name "Net-(R5-Pad1)") (class "Default")
      (node (ref "R5") (pin "1") (pinfunction "1_1") (pintype "passive"))
      (node (ref "RJ1") (pin "Y+") (pinfunction "Y+_Y+") (pintype "bidirectional"))
    )
    (net (code "43") (name "Net-(TERMB-S)") (class "Default")
      (node (ref "R17") (pin "2") (pinfunction "2_2") (pintype "passive"))
      (node (ref "TERM") (pin "2") (pinfunction "S_2") (pintype "passive"))
    )
    (net (code "44") (name "RAM_CS") (class "Default")
      (node (ref "IC1") (pin "18") (pinfunction "RC7/RX/DT_18") (pintype "bidirectional"))
      (node (ref "IC6") (pin "1") (pinfunction "CS_1") (pintype "input"))
    )
    (net (code "45") (name "ROM_CS1") (class "Default")
      (node (ref "IC1") (pin "2") (pinfunction "RA0/AN0_2") (pintype "bidirectional"))
      (node (ref "IC7") (pin "4") (pinfunction "/CS_4") (pintype "input"))
      (node (ref "R14") (pin "1") (pinfunction "1_1") (pintype "passive"))
    )
    (net (code "46") (name "SCK") (class "Default")
      (node (ref "IC1") (pin "14") (pinfunction "RC3/SCK/SCL_14") (pintype "bidirectional"))
      (node (ref "IC2") (pin "8") (pinfunction "SCK_8") (pintype "input"))
      (node (ref "IC6") (pin "6") (pinfunction "SCK_6") (pintype "input"))
      (node (ref "IC7") (pin "2") (pinfunction "SCK_2") (pintype "input"))
    )
    (net (code "47") (name "TPIN+") (class "Default")
      (node (ref "IC2") (pin "13") (pinfunction "TPIN+_13") (pintype "input"))
      (node (ref "R12") (pin "1") (pinfunction "1_1") (pintype "passive"))
      (node (ref "RJ1") (pin "RD+") (pinfunction "RD+_RD+") (pintype "bidirectional"))
    )
    (net (code "48") (name "TPIN-") (class "Default")
      (node (ref "IC2") (pin "12") (pinfunction "TPIN-_12") (pintype "input"))
      (node (ref "R13") (pin "1") (pinfunction "1_1") (pintype "passive"))
      (node (ref "RJ1") (pin "RD-") (pinfunction "RD-_RD-") (pintype "bidirectional"))
    )
    (net (code "49") (name "TPOUT+") (class "Default")
      (node (ref "IC2") (pin "17") (pinfunction "TPOUT+_17") (pintype "output"))
      (node (ref "R9") (pin "2") (pinfunction "2_2") (pintype "passive"))
      (node (ref "RJ1") (pin "TD+") (pinfunction "TD+_TD+") (pintype "bidirectional"))
    )
    (net (code "50") (name "TPOUT-") (class "Default")
      (node (ref "IC2") (pin "16") (pinfunction "TPOUT-_16") (pintype "output"))
      (node (ref "R10") (pin "2") (pinfunction "2_2") (pintype "passive"))
      (node (ref "RJ1") (pin "TD-") (pinfunction "TD-_TD-") (pintype "bidirectional"))
    )
    (net (code "51") (name "VCC") (class "Default")
      (node (ref "C13") (pin "2") (pinfunction "2_2") (pintype "passive"))
      (node (ref "C16") (pin "2") (pinfunction "2_2") (pintype "passive"))
      (node (ref "C2") (pin "+") (pinfunction "+_+") (pintype "passive"))
      (node (ref "C23") (pin "1") (pinfunction "1_1") (pintype "passive"))
      (node (ref "C3") (pin "2") (pinfunction "2_2") (pintype "passive"))
      (node (ref "C5") (pin "1") (pinfunction "1_1") (pintype "passive"))
      (node (ref "C9") (pin "2") (pinfunction "2_2") (pintype "passive"))
      (node (ref "IC1") (pin "20") (pinfunction "VDD_20") (pintype "power_in"))
      (node (ref "IC2") (pin "15") (pinfunction "VDDTX_15") (pintype "power_in"))
      (node (ref "IC2") (pin "19") (pinfunction "VDDRX_19") (pintype "power_in"))
      (node (ref "IC2") (pin "20") (pinfunction "VDDPLL_20") (pintype "power_in"))
      (node (ref "IC2") (pin "25") (pinfunction "VDDOSC_25") (pintype "power_in"))
      (node (ref "IC2") (pin "28") (pinfunction "VDD_28") (pintype "power_in"))
      (node (ref "IC4") (pin "4") (pinfunction "FB_4") (pintype "input"))
      (node (ref "IC5") (pin "2") (pinfunction "VCC_2") (pintype "power_in"))
      (node (ref "IC6") (pin "7") (pinfunction "HOLD_7") (pintype "input"))
      (node (ref "IC6") (pin "8") (pinfunction "VCC_8") (pintype "power_in"))
      (node (ref "IC7") (pin "3") (pinfunction "/RESET_3") (pintype "input"))
      (node (ref "IC7") (pin "5") (pinfunction "/WP_5") (pintype "input"))
      (node (ref "IC7") (pin "6") (pinfunction "VCC_6") (pintype "power_in"))
      (node (ref "J3") (pin "2") (pinfunction "2_2") (pintype "passive"))
      (node (ref "L1") (pin "2") (pinfunction "2_2") (pintype "passive"))
      (node (ref "L2") (pin "2") (pinfunction "2_2") (pintype "passive"))
      (node (ref "R11") (pin "2") (pinfunction "2_2") (pintype "passive"))
      (node (ref "R14") (pin "2") (pinfunction "2_2") (pintype "passive"))
      (node (ref "R19") (pin "1") (pinfunction "1_1") (pintype "passive"))
      (node (ref "R2") (pin "2") (pinfunction "2_2") (pintype "passive"))
      (node (ref "R4") (pin "2") (pinfunction "2_2") (pintype "passive"))
      (node (ref "R6") (pin "1") (pinfunction "1_1") (pintype "passive"))
      (node (ref "R7") (pin "1") (pinfunction "1_1") (pintype "passive"))
    )
    (net (code "52") (name "VIN2") (class "Default")
      (node (ref "C1") (pin "+") (pinfunction "+_+") (pintype "passive"))
      (node (ref "D1") (pin "C") (pinfunction "C_C") (pintype "passive"))
      (node (ref "IC4") (pin "1") (pinfunction "VIN_1") (pintype "power_in"))
    )
    (net (code "53") (name "VREF") (class "Default")
      (node (ref "IC3") (pin "5") (pinfunction "VREF_5") (pintype "power_in"))
    )
    (net (code "54") (name "unconnected-(IC2-CLKOUT-Pad3)") (class "Default")
      (node (ref "IC2") (pin "3") (pinfunction "CLKOUT_3") (pintype "output"))
    )
    (net (code "55") (name "unconnected-(IC6-NC-Pad3)") (class "Default")
      (node (ref "IC6") (pin "3") (pinfunction "NC_3") (pintype "no_connect"))
    )
    (net (code "56") (name "unconnected-(J3-Pad6)") (class "Default")
      (node (ref "J3") (pin "6") (pinfunction "6_6") (pintype "passive"))
    )
    (net (code "57") (name "unconnected-(RJ1-PadNC)") (class "Default")
      (node (ref "RJ1") (pin "NC") (pinfunction "NC_NC") (pintype "bidirectional"))
    )
    (net (code "58") (name "unconnected-(RJ1-PadP5)") (class "Default")
      (node (ref "RJ1") (pin "P5") (pinfunction "P5_P5") (pintype "bidirectional"))
    )
    (net (code "59") (name "unconnected-(RJ1-PadSHIELD0)") (class "Default")
      (node (ref "RJ1") (pin "SHIELD0") (pinfunction "SHIELD0_SHIELD0") (pintype "bidirectional"))
    )
    (net (code "60") (name "unconnected-(RJ1-PadSHIELD1)") (class "Default")
      (node (ref "RJ1") (pin "SHIELD1") (pinfunction "SHIELD1_SHIELD1") (pintype "bidirectional"))
    )
  )
)
